# M5_Stick_LocoNet_Interface_2020-05-23_20.net
KiCad netlist of a schematic drawn in EasyEDA
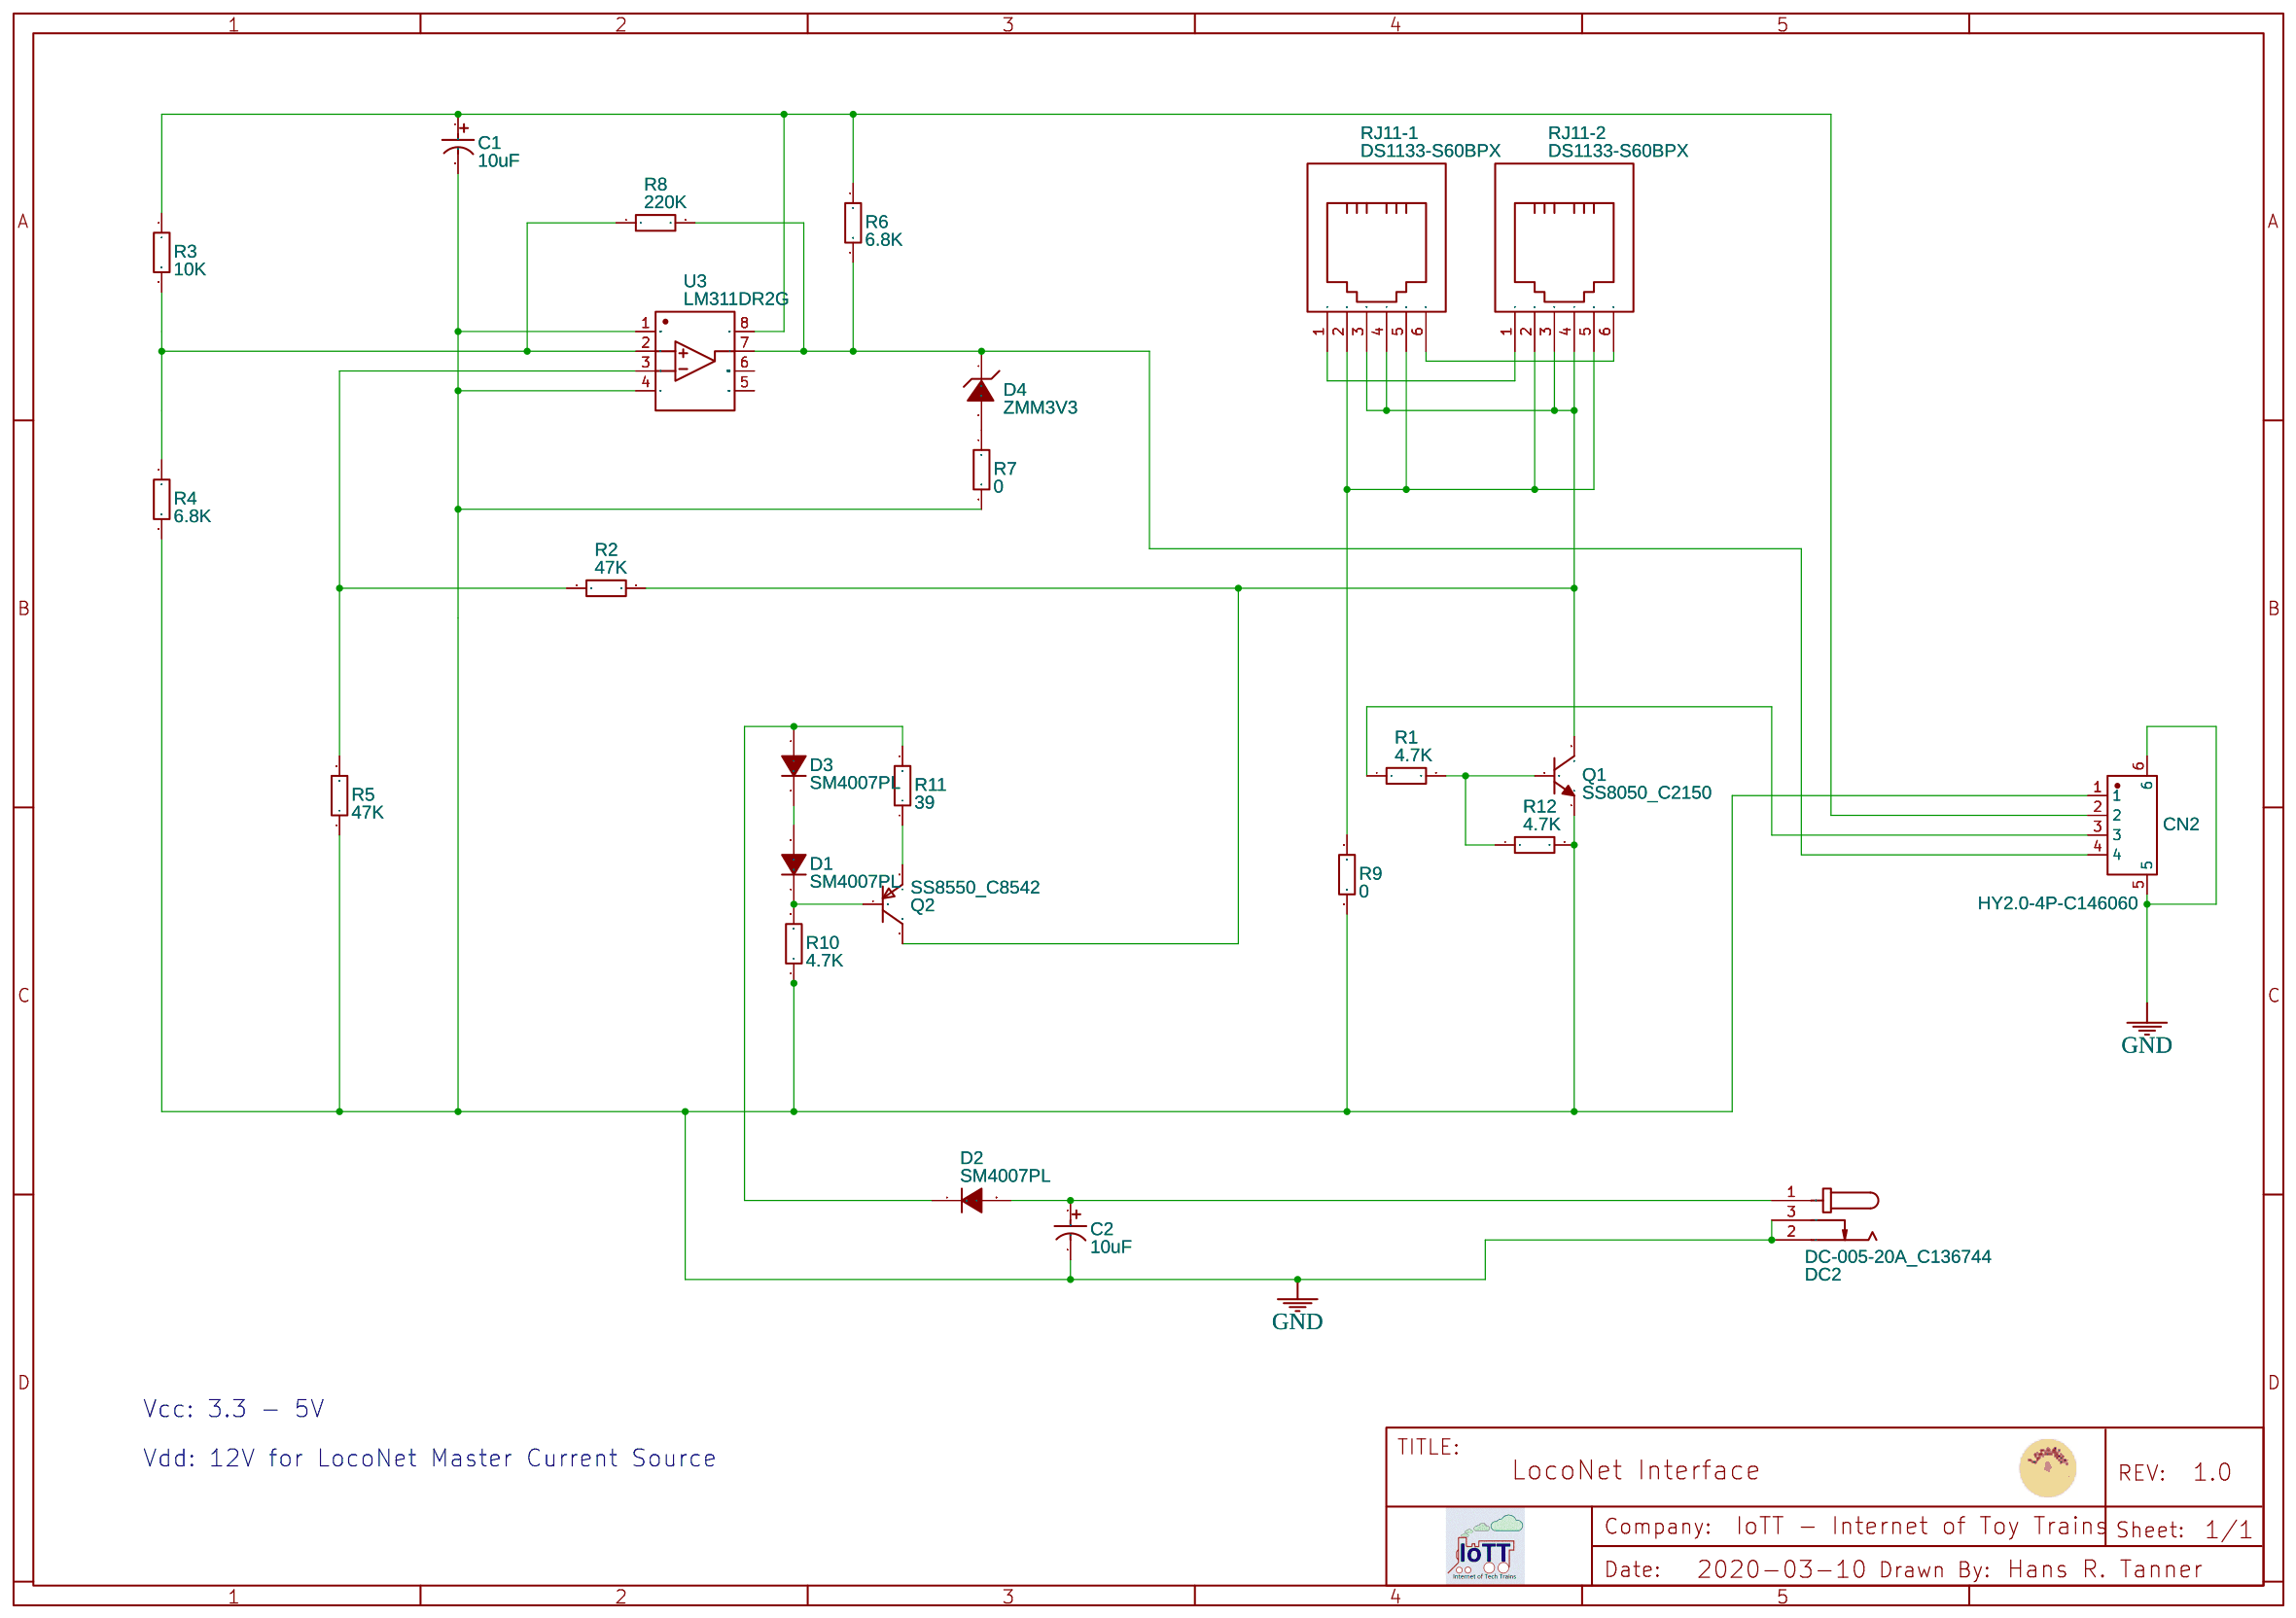
[diagram p0: schematic sheet]

(export (version "E")
  (design (tool "Eeschema 10.0.6"))
  (components
    (comp (ref "C1")
      (value "10uF")
      (fields
        (field (name "BOM_Manufacturer Part") "VE-100M1ETR-0405")
        (field (name "BOM_Supplier Part") "C134721")
      )
      (libsource (lib "") (part "VE-100M1ETR-0405"))
    )
    (comp (ref "C2")
      (value "10uF")
      (fields
        (field (name "BOM_Manufacturer Part") "VE-100M1ETR-0405")
        (field (name "BOM_Supplier Part") "C134721")
      )
      (libsource (lib "") (part "VE-100M1ETR-0405"))
    )
    (comp (ref "CN2")
      (value "HY2.0-4P-C146060")
      (fields (field (name "BOM_Supplier Part") "C146060"))
      (libsource (lib "") (part "HY2.0-4P-C146060"))
    )
    (comp (ref "D1")
      (value "SM4007PL")
      (fields (field (name "BOM_Supplier Part") "C64898"))
      (libsource (lib "") (part "SM4007PL"))
    )
    (comp (ref "D2")
      (value "SM4007PL")
      (fields (field (name "BOM_Supplier Part") "C64898"))
      (libsource (lib "") (part "SM4007PL_1"))
    )
    (comp (ref "D3")
      (value "SM4007PL")
      (fields (field (name "BOM_Supplier Part") "C64898"))
      (libsource (lib "") (part "SM4007PL"))
    )
    (comp (ref "D4")
      (value "ZMM3V3")
      (fields (field (name "BOM_Supplier Part") "C8056"))
      (libsource (lib "") (part "ZMM3V3"))
    )
    (comp (ref "DC2")
      (value "DC-005-20A_C136744")
      (fields
        (field (name "BOM_Manufacturer Part") "DC-005-20A")
        (field (name "BOM_Supplier Part") "C136744")
      )
      (libsource (lib "") (part "DC-005-20A_C136744"))
    )
    (comp (ref "Q1")
      (value "SS8050_C2150")
      (fields (field (name "BOM_Manufacturer Part") "SS8050") (field (name "BOM_Supplier Part") "C2150"))
      (libsource (lib "") (part "SS8050_C2150"))
    )
    (comp (ref "Q2")
      (value "SS8550_C8542")
      (fields (field (name "BOM_Manufacturer Part") "SS8550") (field (name "BOM_Supplier Part") "C8542"))
      (libsource (lib "") (part "SS8550_C8542"))
    )
    (comp (ref "R1")
      (value "4.7K")
      (fields
        (field (name "BOM_Manufacturer Part") "0603WAF4701T5E")
        (field (name "BOM_Supplier Part") "C23162")
      )
      (libsource (lib "") (part "0603WAF4701T5E_1"))
    )
    (comp (ref "R2")
      (value "47K")
      (fields
        (field (name "BOM_Manufacturer Part") "0603WAF4702T5E")
        (field (name "BOM_Supplier Part") "C25819")
      )
      (libsource (lib "") (part "0603WAF4702T5E_1"))
    )
    (comp (ref "R3")
      (value "10K")
      (fields
        (field (name "BOM_Manufacturer Part") "0603WAF1002T5E")
        (field (name "BOM_Supplier Part") "C25804")
      )
      (libsource (lib "") (part "0603WAF1002T5E"))
    )
    (comp (ref "R4")
      (value "6.8K")
      (fields
        (field (name "BOM_Manufacturer Part") "0603WAF6801T5E")
        (field (name "BOM_Supplier Part") "C23212")
      )
      (libsource (lib "") (part "0603WAF6801T5E"))
    )
    (comp (ref "R5")
      (value "47K")
      (fields
        (field (name "BOM_Manufacturer Part") "0603WAF4702T5E")
        (field (name "BOM_Supplier Part") "C25819")
      )
      (libsource (lib "") (part "0603WAF4702T5E"))
    )
    (comp (ref "R6")
      (value "6.8K")
      (fields
        (field (name "BOM_Manufacturer Part") "0603WAF6801T5E")
        (field (name "BOM_Supplier Part") "C23212")
      )
      (libsource (lib "") (part "0603WAF6801T5E"))
    )
    (comp (ref "R7")
      (value "0")
      (fields
        (field (name "BOM_Manufacturer Part") "0402WGF0000TCE")
        (field (name "BOM_Supplier Part") "C17168")
      )
      (libsource (lib "") (part "0402WGF0000TCE"))
    )
    (comp (ref "R8")
      (value "220K")
      (fields
        (field (name "BOM_Manufacturer Part") "0603WAF2203T5E")
        (field (name "BOM_Supplier Part") "C22961")
      )
      (libsource (lib "") (part "0603WAF2203T5E"))
    )
    (comp (ref "R9")
      (value "0")
      (fields
        (field (name "BOM_Manufacturer Part") "0402WGF0000TCE")
        (field (name "BOM_Supplier Part") "C17168")
      )
      (libsource (lib "") (part "0402WGF0000TCE"))
    )
    (comp (ref "R10")
      (value "4.7K")
      (fields
        (field (name "BOM_Manufacturer Part") "0603WAF4701T5E")
        (field (name "BOM_Supplier Part") "C23162")
      )
      (libsource (lib "") (part "0603WAF4701T5E"))
    )
    (comp (ref "R11")
      (value "39")
      (fields
        (field (name "BOM_Manufacturer Part") "TC0325B390JT5E")
        (field (name "BOM_Supplier Part") "C146566")
      )
      (libsource (lib "") (part "TC0325B390JT5E"))
    )
    (comp (ref "R12")
      (value "4.7K")
      (fields
        (field (name "BOM_Manufacturer Part") "0603WAF4701T5E")
        (field (name "BOM_Supplier Part") "C23162")
      )
      (libsource (lib "") (part "0603WAF4701T5E_1"))
    )
    (comp (ref "RJ11-1")
      (value "DS1133-S60BPX")
      (fields (field (name "BOM_Supplier Part") "C77859"))
      (libsource (lib "") (part "Unknown_690_-680"))
    )
    (comp (ref "RJ11-2")
      (value "DS1133-S60BPX")
      (fields (field (name "BOM_Supplier Part") "C77859"))
      (libsource (lib "") (part "Unknown_785_-680"))
    )
    (comp (ref "U3")
      (value "LM311DR2G")
      (fields (field (name "BOM_Supplier Part") "C231850"))
      (libsource (lib "") (part "LM311DR2G"))
    )
  )
  (nets
    (net (code "1") (name "GND") (class "Default")
      (node (ref "C1") (pin "2") (pinfunction "2_2") (pintype "input"))
      (node (ref "C2") (pin "2") (pinfunction "2_2") (pintype "input"))
      (node (ref "CN2") (pin "1") (pinfunction "1_1") (pintype "unspecified"))
      (node (ref "CN2") (pin "5") (pinfunction "5_5") (pintype "unspecified"))
      (node (ref "CN2") (pin "6") (pinfunction "6_6") (pintype "unspecified"))
      (node (ref "DC2") (pin "2") (pinfunction "2_2") (pintype "unspecified"))
      (node (ref "DC2") (pin "3") (pinfunction "3_3") (pintype "unspecified"))
      (node (ref "Q1") (pin "2") (pinfunction "E_2") (pintype "unspecified"))
      (node (ref "R10") (pin "1") (pinfunction "1_1") (pintype "input"))
      (node (ref "R12") (pin "2") (pinfunction "2_2") (pintype "input"))
      (node (ref "R4") (pin "2") (pinfunction "2_2") (pintype "input"))
      (node (ref "R5") (pin "1") (pinfunction "1_1") (pintype "input"))
      (node (ref "R7") (pin "2") (pinfunction "2_2") (pintype "input"))
      (node (ref "R9") (pin "2") (pinfunction "2_2") (pintype "input"))
      (node (ref "U3") (pin "1") (pinfunction "GND_1") (pintype "unspecified"))
      (node (ref "U3") (pin "4") (pinfunction "VEE_4") (pintype "unspecified"))
    )
    (net (code "2") (name "Net-(CN2-Pad3)") (class "Default")
      (node (ref "CN2") (pin "3") (pinfunction "3_3") (pintype "unspecified"))
      (node (ref "R1") (pin "1") (pinfunction "1_1") (pintype "input"))
    )
    (net (code "3") (name "Net-(D1-A)") (class "Default")
      (node (ref "D1") (pin "2") (pinfunction "A_2") (pintype "unspecified"))
      (node (ref "D3") (pin "1") (pinfunction "C_1") (pintype "unspecified"))
    )
    (net (code "4") (name "Net-(D1-C)") (class "Default")
      (node (ref "D1") (pin "1") (pinfunction "C_1") (pintype "unspecified"))
      (node (ref "Q2") (pin "1") (pinfunction "B_1") (pintype "unspecified"))
      (node (ref "R10") (pin "2") (pinfunction "2_2") (pintype "input"))
    )
    (net (code "5") (name "Net-(D2-A)") (class "Default")
      (node (ref "C2") (pin "1") (pinfunction "1_1") (pintype "input"))
      (node (ref "D2") (pin "2") (pinfunction "A_2") (pintype "unspecified"))
      (node (ref "DC2") (pin "1") (pinfunction "1_1") (pintype "unspecified"))
    )
    (net (code "6") (name "Net-(D2-C)") (class "Default")
      (node (ref "D2") (pin "1") (pinfunction "C_1") (pintype "unspecified"))
      (node (ref "D3") (pin "2") (pinfunction "A_2") (pintype "unspecified"))
      (node (ref "R11") (pin "2") (pinfunction "2_2") (pintype "input"))
    )
    (net (code "7") (name "Net-(D4-A)") (class "Default")
      (node (ref "D4") (pin "2") (pinfunction "A_2") (pintype "unspecified"))
      (node (ref "R7") (pin "1") (pinfunction "1_1") (pintype "input"))
    )
    (net (code "8") (name "Net-(D4-C)") (class "Default")
      (node (ref "CN2") (pin "4") (pinfunction "4_4") (pintype "unspecified"))
      (node (ref "D4") (pin "1") (pinfunction "C_1") (pintype "unspecified"))
      (node (ref "R6") (pin "2") (pinfunction "2_2") (pintype "input"))
      (node (ref "R8") (pin "2") (pinfunction "2_2") (pintype "input"))
      (node (ref "U3") (pin "7") (pinfunction "7_7") (pintype "unspecified"))
    )
    (net (code "9") (name "Net-(Q1-B)") (class "Default")
      (node (ref "Q1") (pin "1") (pinfunction "B_1") (pintype "unspecified"))
      (node (ref "R1") (pin "2") (pinfunction "2_2") (pintype "input"))
      (node (ref "R12") (pin "1") (pinfunction "1_1") (pintype "input"))
    )
    (net (code "10") (name "Net-(Q1-C)") (class "Default")
      (node (ref "Q1") (pin "3") (pinfunction "C_3") (pintype "unspecified"))
      (node (ref "Q2") (pin "3") (pinfunction "C_3") (pintype "unspecified"))
      (node (ref "R2") (pin "2") (pinfunction "2_2") (pintype "input"))
      (node (ref "RJ11-1") (pin "3") (pinfunction "3_3") (pintype "unspecified"))
      (node (ref "RJ11-1") (pin "4") (pinfunction "4_4") (pintype "unspecified"))
      (node (ref "RJ11-2") (pin "3") (pinfunction "3_3") (pintype "unspecified"))
      (node (ref "RJ11-2") (pin "4") (pinfunction "4_4") (pintype "unspecified"))
    )
    (net (code "11") (name "Net-(Q2-E)") (class "Default")
      (node (ref "Q2") (pin "2") (pinfunction "E_2") (pintype "unspecified"))
      (node (ref "R11") (pin "1") (pinfunction "1_1") (pintype "input"))
    )
    (net (code "12") (name "Net-(R2-Pad1)") (class "Default")
      (node (ref "R2") (pin "1") (pinfunction "1_1") (pintype "input"))
      (node (ref "R5") (pin "2") (pinfunction "2_2") (pintype "input"))
      (node (ref "U3") (pin "3") (pinfunction "3_3") (pintype "unspecified"))
    )
    (net (code "13") (name "Net-(R3-Pad2)") (class "Default")
      (node (ref "R3") (pin "2") (pinfunction "2_2") (pintype "input"))
      (node (ref "R4") (pin "1") (pinfunction "1_1") (pintype "input"))
      (node (ref "R8") (pin "1") (pinfunction "1_1") (pintype "input"))
      (node (ref "U3") (pin "2") (pinfunction "2_2") (pintype "unspecified"))
    )
    (net (code "14") (name "Net-(R9-Pad1)") (class "Default")
      (node (ref "R9") (pin "1") (pinfunction "1_1") (pintype "input"))
      (node (ref "RJ11-1") (pin "2") (pinfunction "2_2") (pintype "unspecified"))
      (node (ref "RJ11-1") (pin "5") (pinfunction "5_5") (pintype "unspecified"))
      (node (ref "RJ11-2") (pin "2") (pinfunction "2_2") (pintype "unspecified"))
      (node (ref "RJ11-2") (pin "5") (pinfunction "5_5") (pintype "unspecified"))
    )
    (net (code "15") (name "Net-(RJ11-1-Pad1)") (class "Default")
      (node (ref "RJ11-1") (pin "1") (pinfunction "1_1") (pintype "unspecified"))
      (node (ref "RJ11-2") (pin "1") (pinfunction "1_1") (pintype "unspecified"))
    )
    (net (code "16") (name "Net-(RJ11-1-Pad6)") (class "Default")
      (node (ref "RJ11-1") (pin "6") (pinfunction "6_6") (pintype "unspecified"))
      (node (ref "RJ11-2") (pin "6") (pinfunction "6_6") (pintype "unspecified"))
    )
    (net (code "17") (name "Net-(U3-VCC)") (class "Default")
      (node (ref "C1") (pin "1") (pinfunction "1_1") (pintype "input"))
      (node (ref "CN2") (pin "2") (pinfunction "2_2") (pintype "unspecified"))
      (node (ref "R3") (pin "1") (pinfunction "1_1") (pintype "input"))
      (node (ref "R6") (pin "1") (pinfunction "1_1") (pintype "input"))
      (node (ref "U3") (pin "8") (pinfunction "VCC_8") (pintype "unspecified"))
    )
    (net (code "18") (name "unconnected-(U3-BALANCE-Pad5)") (class "Default")
      (node (ref "U3") (pin "5") (pinfunction "BALANCE_5") (pintype "unspecified"))
    )
    (net (code "19") (name "unconnected-(U3-BALANCE{slash}STROBE-Pad6)") (class "Default")
      (node (ref "U3") (pin "6") (pinfunction "BALANCE/STROBE_6") (pintype "unspecified"))
    )
  )
)
